# SH11_-_CAN.net
KiCad netlist of a schematic drawn in Altium Designer
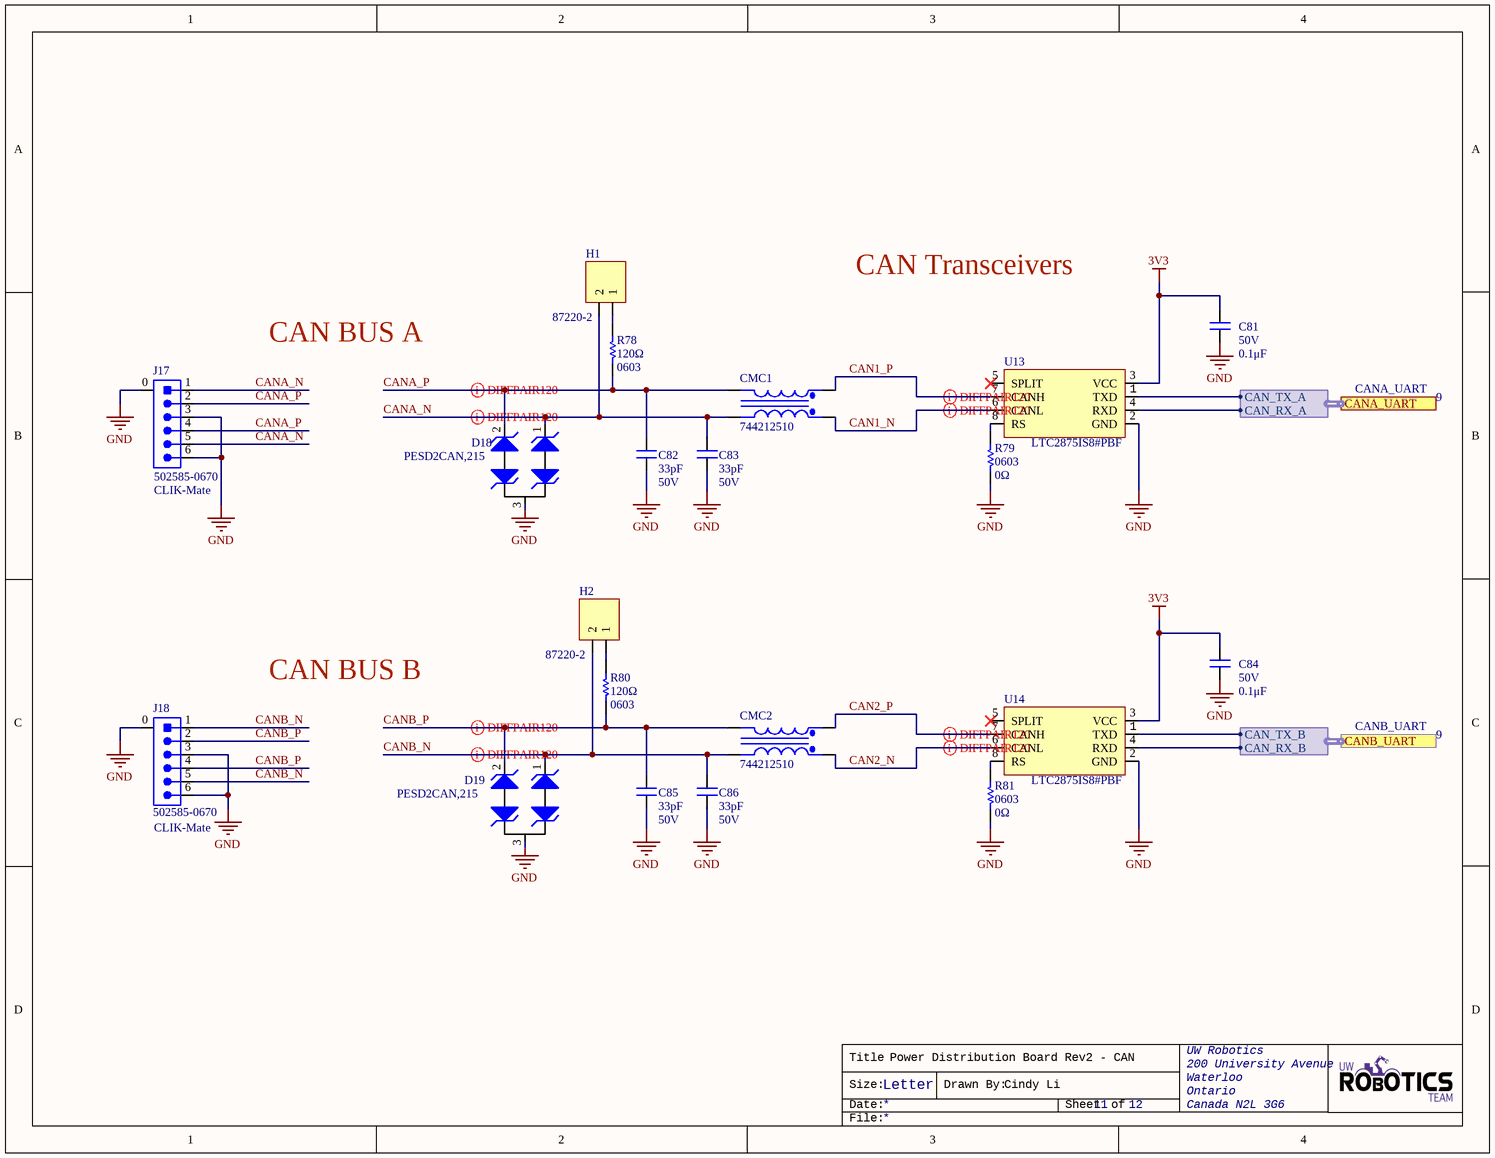
[diagram p0: SH11 - CAN.SchDoc]

(export (version "E")
  (design (tool "Eeschema 10.0.6"))
  (components
    (comp (ref "C81")
      (value "0.1μF")
      (footprint "CAP0603")
      (description "CAP CER 0.1UF 50V X7R 0603")
      (fields (field (name "VOLTAGE RATING") "50V") (field (name "Comment") "CAP_0.1uF_50V_0603"))
      (libsource (lib "UWRT_Schematic_Library_2020") (part "CAP_0.1uF_50V_0603"))
    )
    (comp (ref "C82")
      (value "33pF")
      (footprint "CAP0603")
      (description "CAP CER 33PF 50V C0G/NP0")
      (fields
        (field (name "TOLERANCE") "5%")
        (field (name "VOLTAGE") "50V")
        (field (name "Comment") "CAP_33pF_50V_0603")
      )
      (libsource (lib "UWRT_Schematic_Library_2020") (part "CAP_33pF_50V_0603"))
    )
    (comp (ref "C83")
      (value "33pF")
      (footprint "CAP0603")
      (description "CAP CER 33PF 50V C0G/NP0")
      (fields
        (field (name "TOLERANCE") "5%")
        (field (name "VOLTAGE") "50V")
        (field (name "Comment") "CAP_33pF_50V_0603")
      )
      (libsource (lib "UWRT_Schematic_Library_2020") (part "CAP_33pF_50V_0603"))
    )
    (comp (ref "C84")
      (value "0.1μF")
      (footprint "CAP0603")
      (description "CAP CER 0.1UF 50V X7R 0603")
      (fields (field (name "VOLTAGE RATING") "50V") (field (name "Comment") "CAP_0.1uF_50V_0603"))
      (libsource (lib "UWRT_Schematic_Library_2020") (part "CAP_0.1uF_50V_0603"))
    )
    (comp (ref "C85")
      (value "33pF")
      (footprint "CAP0603")
      (description "CAP CER 33PF 50V C0G/NP0")
      (fields
        (field (name "TOLERANCE") "5%")
        (field (name "VOLTAGE") "50V")
        (field (name "Comment") "CAP_33pF_50V_0603")
      )
      (libsource (lib "UWRT_Schematic_Library_2020") (part "CAP_33pF_50V_0603"))
    )
    (comp (ref "C86")
      (value "33pF")
      (footprint "CAP0603")
      (description "CAP CER 33PF 50V C0G/NP0")
      (fields
        (field (name "TOLERANCE") "5%")
        (field (name "VOLTAGE") "50V")
        (field (name "Comment") "CAP_33pF_50V_0603")
      )
      (libsource (lib "UWRT_Schematic_Library_2020") (part "CAP_33pF_50V_0603"))
    )
    (comp (ref "CMC1")
      (value "CMC_51uH")
      (footprint "744212510")
      (description "CMC 51uH 300MA 2LN SMD")
      (fields (field (name "MANUFACTURER PART NUMBER 1") "744212510") (field (name "TOLERANCE") "50%"))
      (libsource (lib "UWRT_Schematic_Library_2020") (part "CMC_51uH"))
    )
    (comp (ref "CMC2")
      (value "CMC_51uH")
      (footprint "744212510")
      (description "CMC 51uH 300MA 2LN SMD")
      (fields (field (name "MANUFACTURER PART NUMBER 1") "744212510") (field (name "TOLERANCE") "50%"))
      (libsource (lib "UWRT_Schematic_Library_2020") (part "CMC_51uH"))
    )
    (comp (ref "D18")
      (value "TVS_DIODE_CAN")
      (footprint "TVS_DIODE_CAN")
      (description "TVS DIODE 24V 41V SOT323-3")
      (fields (field (name "MANUFACTURER PART NUMBER 1") "PESD2CAN,215"))
      (libsource (lib "UWRT_Schematic_Library_2020") (part "TVS_DIODE_CAN"))
    )
    (comp (ref "D19")
      (value "TVS_DIODE_CAN")
      (footprint "TVS_DIODE_CAN")
      (description "TVS DIODE 24V 41V SOT323-3")
      (fields (field (name "MANUFACTURER PART NUMBER 1") "PESD2CAN,215"))
      (libsource (lib "UWRT_Schematic_Library_2020") (part "TVS_DIODE_CAN"))
    )
    (comp (ref "H1")
      (value "JUMPER_2")
      (footprint "HDR1X2")
      (description "HEADER 2X1")
      (fields (field (name "MANUFACTURER PART NUMBER 1") "87220-2"))
      (libsource (lib "UWRT_Schematic_Library_2020") (part "JUMPER_2"))
    )
    (comp (ref "H2")
      (value "JUMPER_2")
      (footprint "HDR1X2")
      (description "HEADER 2X1")
      (fields (field (name "MANUFACTURER PART NUMBER 1") "87220-2"))
      (libsource (lib "UWRT_Schematic_Library_2020") (part "JUMPER_2"))
    )
    (comp (ref "J17")
      (value "CON_6M_SM_RA_1.5mm")
      (footprint "MOLEX-5025850670")
      (description "CONN HEADER SMD RIGHT ANGLE 1.5 MM PITCH")
      (fields
        (field (name "MANUFACTOR NUMBER") "502585-0670")
        (field (name "MANUFACTURER") "Molex")
        (field (name "FAMILY") "CLIK-Mate")
      )
      (libsource (lib "UWRT_Schematic_Library_2020") (part "CON_6M_SM_RA_1.5mm"))
    )
    (comp (ref "J18")
      (value "CON_6M_SM_RA_1.5mm")
      (footprint "MOLEX-5025850670")
      (description "CONN HEADER SMD RIGHT ANGLE 1.5 MM PITCH")
      (fields
        (field (name "MANUFACTOR NUMBER") "502585-0670")
        (field (name "MANUFACTURER") "Molex")
        (field (name "FAMILY") "CLIK-Mate")
      )
      (libsource (lib "UWRT_Schematic_Library_2020") (part "CON_6M_SM_RA_1.5mm"))
    )
    (comp (ref "R78")
      (value "120Ω")
      (footprint "RESC0603(1608)_N")
      (description "RES 120 OHM 5% 1/10W 0603")
      (fields
        (field (name "TOLERANCE") "5%")
        (field (name "CASE CODE (IMPERIAL)") "0603")
        (field (name "Comment") "RES_120Ω_0603")
      )
      (libsource (lib "UWRT_Schematic_Library_2020") (part "RES_120Ω_0603_5%"))
    )
    (comp (ref "R79")
      (value "0Ω")
      (footprint "RESC0603(1608)_N")
      (description "RES 0 OHM JUMPER 1/10W 0603")
      (fields (field (name "CASE CODE (IMPERIAL)") "0603") (field (name "Comment") "RES_0Ω_0603"))
      (libsource (lib "UWRT_Schematic_Library_2020") (part "RES_0Ω_0603"))
    )
    (comp (ref "R80")
      (value "120Ω")
      (footprint "RESC0603(1608)_N")
      (description "RES 120 OHM 5% 1/10W 0603")
      (fields
        (field (name "TOLERANCE") "5%")
        (field (name "CASE CODE (IMPERIAL)") "0603")
        (field (name "Comment") "RES_120Ω_0603")
      )
      (libsource (lib "UWRT_Schematic_Library_2020") (part "RES_120Ω_0603_5%"))
    )
    (comp (ref "R81")
      (value "0Ω")
      (footprint "RESC0603(1608)_N")
      (description "RES 0 OHM JUMPER 1/10W 0603")
      (fields (field (name "CASE CODE (IMPERIAL)") "0603") (field (name "Comment") "RES_0Ω_0603"))
      (libsource (lib "UWRT_Schematic_Library_2020") (part "RES_0Ω_0603"))
    )
    (comp (ref "U13")
      (value "IC TXRX CAN")
      (footprint "LT-S8_N")
      (description "IC TXRX CAN 4MBPS 8SO")
      (fields (field (name "MANUFACTURER PART NUMBER 1") "LTC2875IS8#PBF"))
      (libsource (lib "UWRT_Schematic_Library_2020") (part "LTC2875"))
    )
    (comp (ref "U14")
      (value "IC TXRX CAN")
      (footprint "LT-S8_N")
      (description "IC TXRX CAN 4MBPS 8SO")
      (fields (field (name "MANUFACTURER PART NUMBER 1") "LTC2875IS8#PBF"))
      (libsource (lib "UWRT_Schematic_Library_2020") (part "LTC2875"))
    )
  )
  (nets
    (net (code "3") (name "/CAN1_N") (class "Default")
      (node (ref "CMC1") (pin "1") (pinfunction "Pri+_1") (pintype "passive"))
      (node (ref "U13") (pin "6") (pinfunction "CANL_6") (pintype "passive"))
    )
    (net (code "4") (name "/CAN1_P") (class "Default")
      (node (ref "CMC1") (pin "3") (pinfunction "Sec+_3") (pintype "passive"))
      (node (ref "U13") (pin "7") (pinfunction "CANH_7") (pintype "passive"))
    )
    (net (code "5") (name "/CAN2_N") (class "Default")
      (node (ref "CMC2") (pin "1") (pinfunction "Pri+_1") (pintype "passive"))
      (node (ref "U14") (pin "6") (pinfunction "CANL_6") (pintype "passive"))
    )
    (net (code "6") (name "/CAN2_P") (class "Default")
      (node (ref "CMC2") (pin "3") (pinfunction "Sec+_3") (pintype "passive"))
      (node (ref "U14") (pin "7") (pinfunction "CANH_7") (pintype "passive"))
    )
    (net (code "7") (name "/CANA_N") (class "Default")
      (node (ref "C83") (pin "2") (pinfunction "2_2") (pintype "passive"))
      (node (ref "CMC1") (pin "5") (pinfunction "Pri-_5") (pintype "passive"))
      (node (ref "D18") (pin "1") (pinfunction "1_1") (pintype "passive"))
      (node (ref "H1") (pin "2") (pinfunction "2_2") (pintype "passive"))
      (node (ref "J17") (pin "1") (pinfunction "1_1") (pintype "passive"))
      (node (ref "J17") (pin "5") (pinfunction "5_5") (pintype "passive"))
    )
    (net (code "8") (name "/CANA_P") (class "Default")
      (node (ref "C82") (pin "2") (pinfunction "2_2") (pintype "passive"))
      (node (ref "CMC1") (pin "4") (pinfunction "Sec-_4") (pintype "passive"))
      (node (ref "D18") (pin "2") (pinfunction "2_2") (pintype "passive"))
      (node (ref "J17") (pin "2") (pinfunction "2_2") (pintype "passive"))
      (node (ref "J17") (pin "4") (pinfunction "4_4") (pintype "passive"))
      (node (ref "R78") (pin "1") (pinfunction "1_1") (pintype "passive"))
    )
    (net (code "9") (name "/CANB_N") (class "Default")
      (node (ref "C86") (pin "2") (pinfunction "2_2") (pintype "passive"))
      (node (ref "CMC2") (pin "5") (pinfunction "Pri-_5") (pintype "passive"))
      (node (ref "D19") (pin "1") (pinfunction "1_1") (pintype "passive"))
      (node (ref "H2") (pin "2") (pinfunction "2_2") (pintype "passive"))
      (node (ref "J18") (pin "1") (pinfunction "1_1") (pintype "passive"))
      (node (ref "J18") (pin "5") (pinfunction "5_5") (pintype "passive"))
    )
    (net (code "10") (name "/CANB_P") (class "Default")
      (node (ref "C85") (pin "2") (pinfunction "2_2") (pintype "passive"))
      (node (ref "CMC2") (pin "4") (pinfunction "Sec-_4") (pintype "passive"))
      (node (ref "D19") (pin "2") (pinfunction "2_2") (pintype "passive"))
      (node (ref "J18") (pin "2") (pinfunction "2_2") (pintype "passive"))
      (node (ref "J18") (pin "4") (pinfunction "4_4") (pintype "passive"))
      (node (ref "R80") (pin "1") (pinfunction "1_1") (pintype "passive"))
    )
    (net (code "11") (name "/CAN_RX_A") (class "Default")
      (node (ref "U13") (pin "4") (pinfunction "RXD_4") (pintype "passive"))
    )
    (net (code "12") (name "/CAN_RX_B") (class "Default")
      (node (ref "U14") (pin "4") (pinfunction "RXD_4") (pintype "passive"))
    )
    (net (code "13") (name "/CAN_TX_A") (class "Default")
      (node (ref "U13") (pin "1") (pinfunction "TXD_1") (pintype "passive"))
    )
    (net (code "14") (name "/CAN_TX_B") (class "Default")
      (node (ref "U14") (pin "1") (pinfunction "TXD_1") (pintype "passive"))
    )
    (net (code "17") (name "3V3") (class "Default")
      (node (ref "C81") (pin "1") (pinfunction "1_1") (pintype "passive"))
      (node (ref "C84") (pin "1") (pinfunction "1_1") (pintype "passive"))
      (node (ref "U13") (pin "3") (pinfunction "VCC_3") (pintype "passive"))
      (node (ref "U14") (pin "3") (pinfunction "VCC_3") (pintype "passive"))
    )
    (net (code "18") (name "GND") (class "Default")
      (node (ref "C81") (pin "2") (pinfunction "2_2") (pintype "passive"))
      (node (ref "C82") (pin "1") (pinfunction "1_1") (pintype "passive"))
      (node (ref "C83") (pin "1") (pinfunction "1_1") (pintype "passive"))
      (node (ref "C84") (pin "2") (pinfunction "2_2") (pintype "passive"))
      (node (ref "C85") (pin "1") (pinfunction "1_1") (pintype "passive"))
      (node (ref "C86") (pin "1") (pinfunction "1_1") (pintype "passive"))
      (node (ref "D18") (pin "3") (pinfunction "3_3") (pintype "passive"))
      (node (ref "D19") (pin "3") (pinfunction "3_3") (pintype "passive"))
      (node (ref "J17") (pin "0") (pinfunction "0_0") (pintype "passive"))
      (node (ref "J17") (pin "3") (pinfunction "3_3") (pintype "passive"))
      (node (ref "J17") (pin "6") (pinfunction "6_6") (pintype "passive"))
      (node (ref "J18") (pin "0") (pinfunction "0_0") (pintype "passive"))
      (node (ref "J18") (pin "3") (pinfunction "3_3") (pintype "passive"))
      (node (ref "J18") (pin "6") (pinfunction "6_6") (pintype "passive"))
      (node (ref "R79") (pin "1") (pinfunction "1_1") (pintype "passive"))
      (node (ref "R81") (pin "1") (pinfunction "1_1") (pintype "passive"))
      (node (ref "U13") (pin "2") (pinfunction "GND_2") (pintype "passive"))
      (node (ref "U14") (pin "2") (pinfunction "GND_2") (pintype "passive"))
    )
    (net (code "19") (name "Net-(H1-Pad1)") (class "Default")
      (node (ref "H1") (pin "1") (pinfunction "1_1") (pintype "passive"))
      (node (ref "R78") (pin "2") (pinfunction "2_2") (pintype "passive"))
    )
    (net (code "20") (name "Net-(H2-Pad1)") (class "Default")
      (node (ref "H2") (pin "1") (pinfunction "1_1") (pintype "passive"))
      (node (ref "R80") (pin "2") (pinfunction "2_2") (pintype "passive"))
    )
    (net (code "21") (name "Net-(U13-RS)") (class "Default")
      (node (ref "R79") (pin "2") (pinfunction "2_2") (pintype "passive"))
      (node (ref "U13") (pin "8") (pinfunction "RS_8") (pintype "passive"))
    )
    (net (code "22") (name "Net-(U14-RS)") (class "Default")
      (node (ref "R81") (pin "2") (pinfunction "2_2") (pintype "passive"))
      (node (ref "U14") (pin "8") (pinfunction "RS_8") (pintype "passive"))
    )
    (net (code "23") (name "unconnected-(U13-SPLIT-Pad5)") (class "Default")
      (node (ref "U13") (pin "5") (pinfunction "SPLIT_5") (pintype "passive+no_connect"))
    )
    (net (code "24") (name "unconnected-(U14-SPLIT-Pad5)") (class "Default")
      (node (ref "U14") (pin "5") (pinfunction "SPLIT_5") (pintype "passive+no_connect"))
    )
  )
)
